# SCH_Arduino_Uno_2023-06-21.net
KiCad netlist of a schematic drawn in EasyEDA
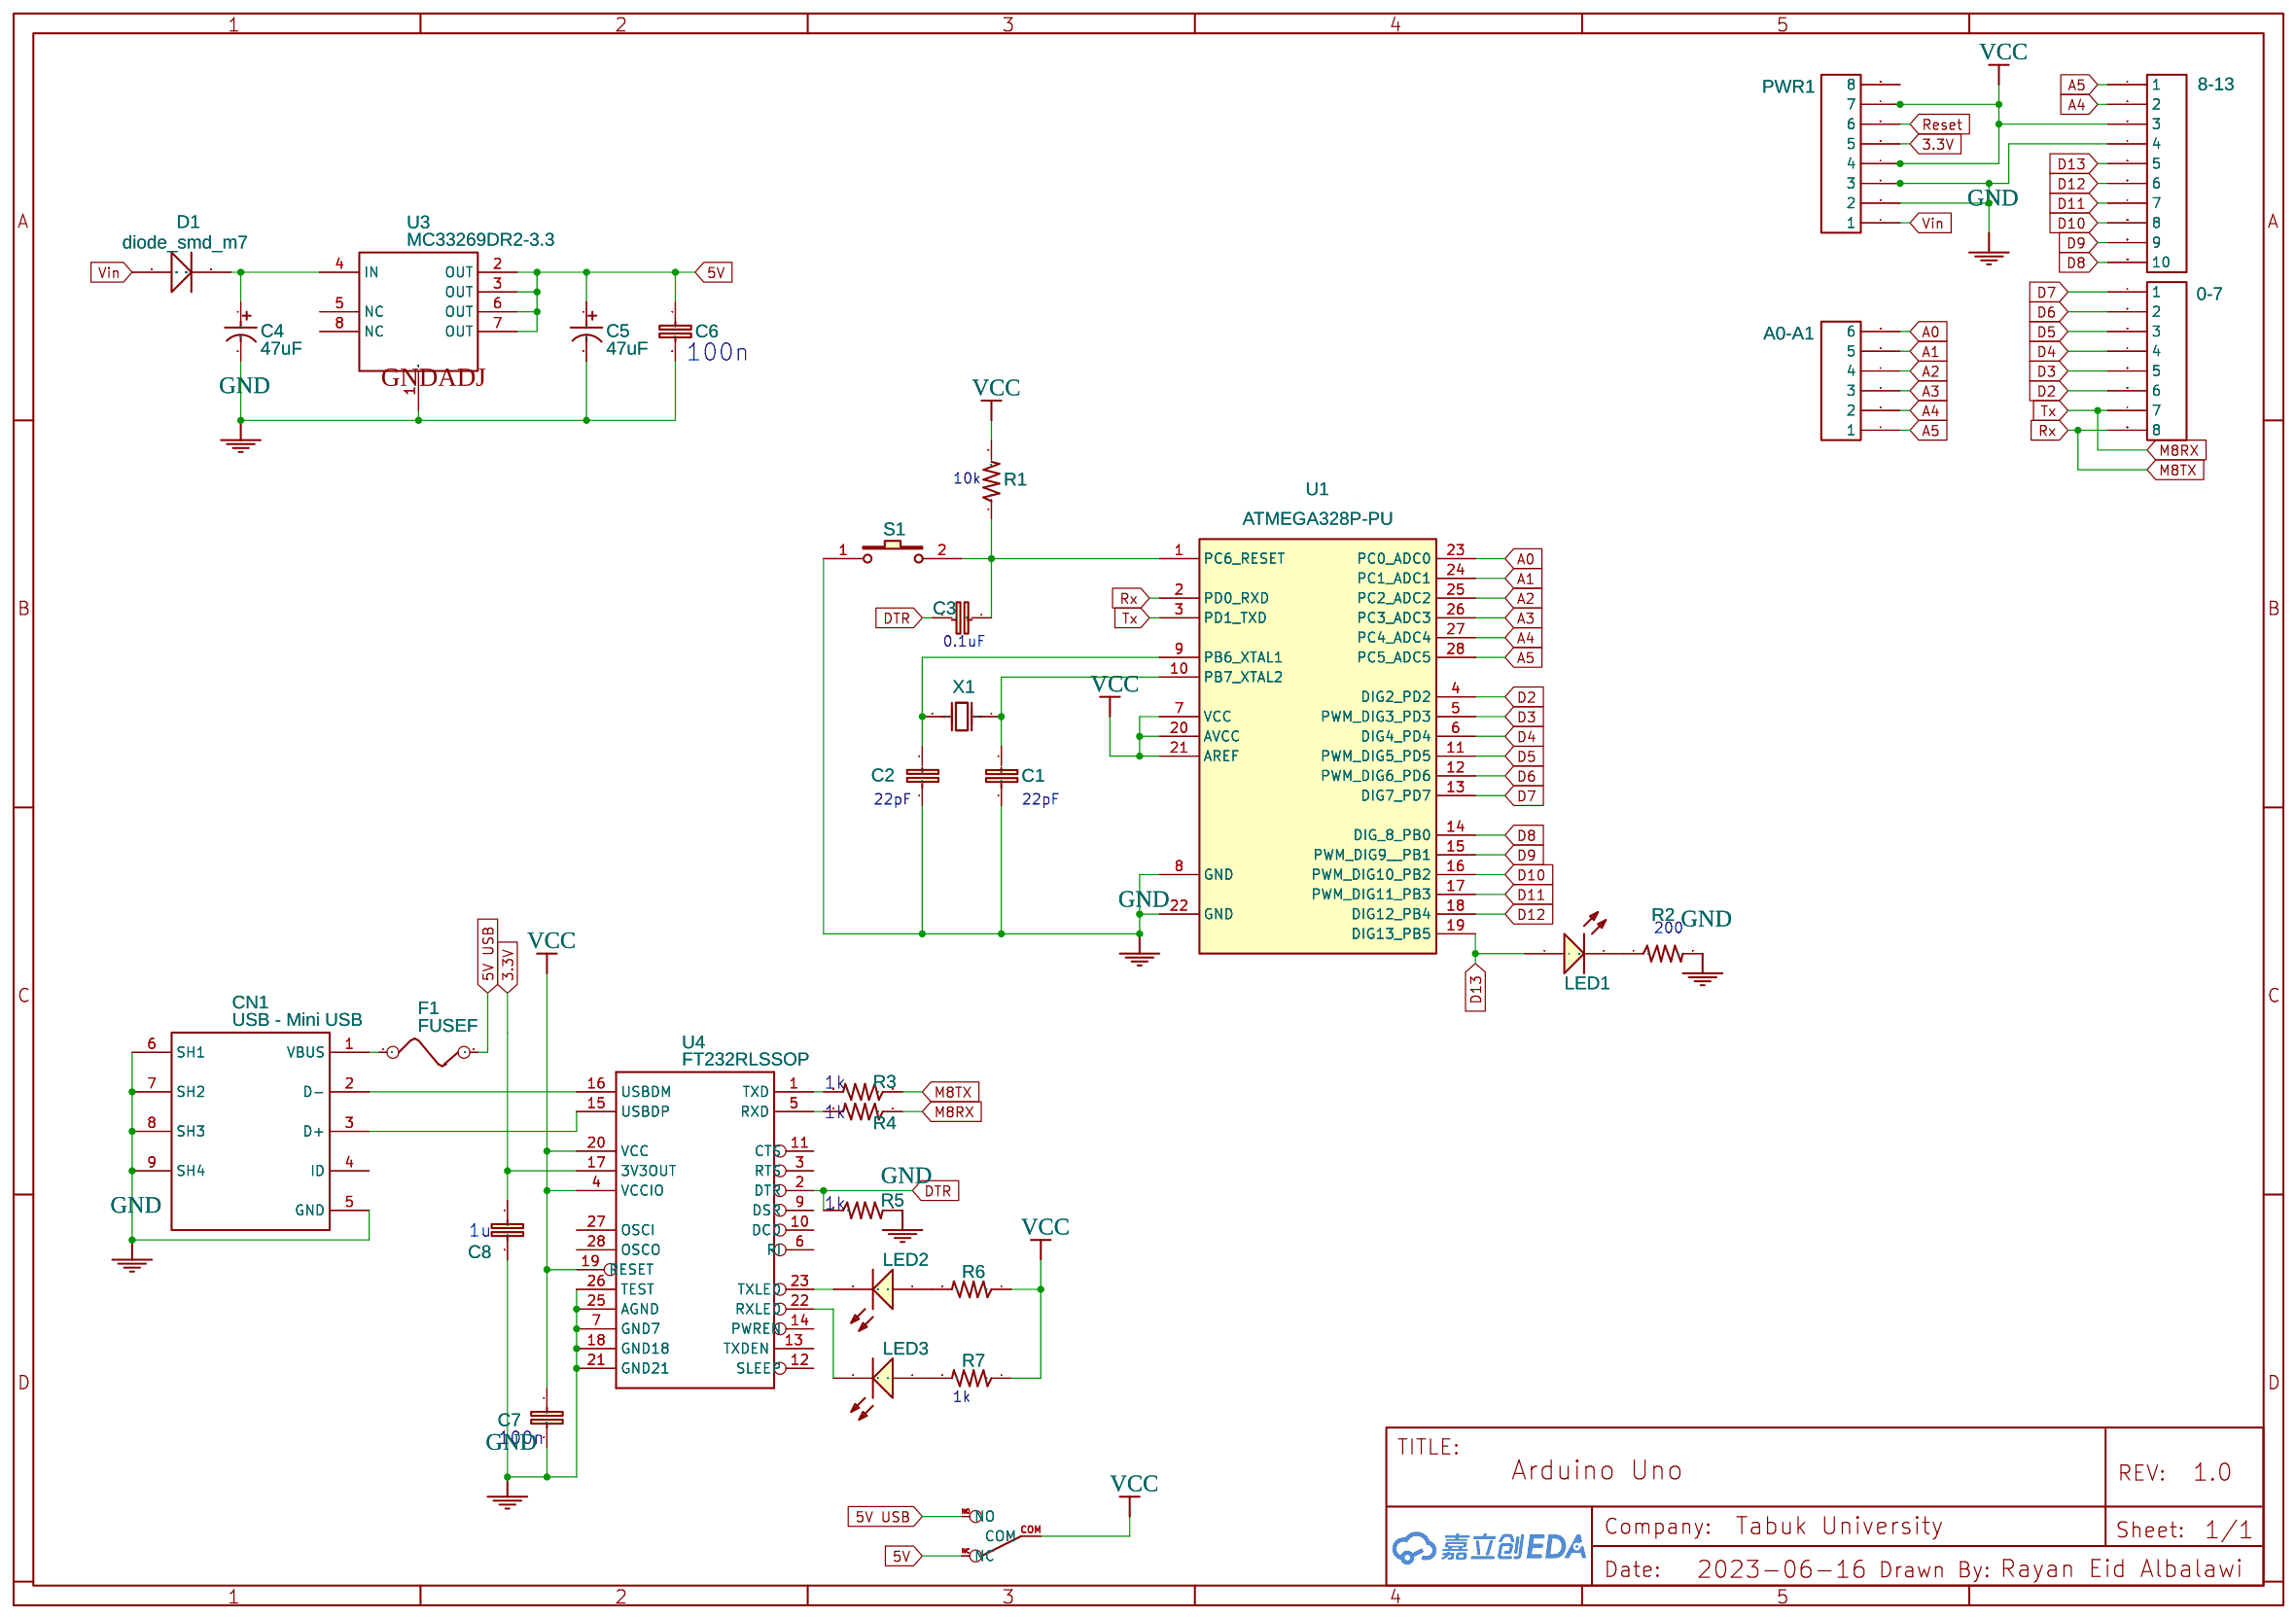
[diagram p0: schematic sheet]

(export (version "E")
  (design (tool "Eeschema 10.0.6"))
  (components
    (comp (ref "0-7")
      (value "0-7")
      (fields (field (name "BOM_Manufacturer Part") "Header2.54mm 1*8P"))
      (libsource (lib "") (part "Unknown_1070_-635"))
    )
    (comp (ref "8-13")
      (value "8-Aref")
      (fields (field (name "BOM_Manufacturer Part") "Headers  Pins2.54mm1*10P"))
      (libsource (lib "") (part "Unknown_1070_-730"))
    )
    (comp (ref "A0-A1")
      (value "Analogs")
      (fields
        (field (name "BOM_Manufacturer Part") "Header-Male-2.54_1x6")
        (field (name "BOM_Supplier Part") "C37208")
      )
      (libsource (lib "") (part "Unknown_945_-615"))
    )
    (comp (ref "C1")
      (value "CAPACITOR_NPOL-0805")
      (fields (field (name "BOM_Manufacturer Part") "?"))
      (libsource (lib "") (part "Unknown_500_-415"))
    )
    (comp (ref "C2")
      (value "CAPACITOR_NPOL-0805")
      (fields (field (name "BOM_Manufacturer Part") "?"))
      (libsource (lib "") (part "Unknown_460_-425"))
    )
    (comp (ref "C3")
      (value "CAPACITOR_NPOL-0805")
      (fields (field (name "BOM_Manufacturer Part") "?"))
      (libsource (lib "") (part "Unknown_485_-500"))
    )
    (comp (ref "C4")
      (value "47uF")
      (fields (field (name "BOM_Manufacturer Part") "EEE-HD1C470AP"))
      (libsource (lib "") (part "Unknown_115_-645"))
    )
    (comp (ref "C5")
      (value "47uF")
      (fields (field (name "BOM_Manufacturer Part") "EEE-HD1C470AP"))
      (libsource (lib "") (part "Unknown_290_-645"))
    )
    (comp (ref "C6")
      (value "CAPACITOR_NPOL-0805")
      (fields (field (name "BOM_Manufacturer Part") "?"))
      (libsource (lib "") (part "Unknown_335_-640"))
    )
    (comp (ref "C7")
      (value "CAPACITOR_NPOL-0805")
      (fields (field (name "BOM_Manufacturer Part") "?"))
      (libsource (lib "") (part "Unknown_270_-90"))
    )
    (comp (ref "C8")
      (value "CAPACITOR_NPOL-0805")
      (fields (field (name "BOM_Manufacturer Part") "?"))
      (libsource (lib "") (part "Unknown_250_-185"))
    )
    (comp (ref "CN1") (value "USB - Mini USB") (libsource (lib "") (part "Unknown_120_-250")))
    (comp (ref "D1")
      (value "diode_smd_m7")
      (fields (field (name "BOM_Manufacturer Part") "?"))
      (libsource (lib "") (part "diode_smd_m7"))
    )
    (comp (ref "F1")
      (value "FUSEF")
      (fields (field (name "BOM_Manufacturer Part") "?"))
      (libsource (lib "") (part "Unknown_215_-280"))
    )
    (comp (ref "LED1")
      (value "17-21/GHC-YR1S2/3T")
      (fields (field (name "BOM_Supplier Part") "E73546"))
      (libsource (lib "") (part "Unknown_785_-330"))
    )
    (comp (ref "LED2")
      (value "17-21/GHC-YR1S2/3T")
      (fields (field (name "BOM_Supplier Part") "E73546"))
      (libsource (lib "") (part "Unknown_445_-160"))
    )
    (comp (ref "LED3")
      (value "17-21/GHC-YR1S2/3T")
      (fields (field (name "BOM_Supplier Part") "E73546"))
      (libsource (lib "") (part "Unknown_445_-115"))
    )
    (comp (ref "PWR1")
      (value "Powers")
      (fields (field (name "BOM_Manufacturer Part") "Header2.54mm 1*8P"))
      (libsource (lib "") (part "Unknown_945_-730"))
    )
    (comp (ref "R1")
      (value "0.22OHM-1_4W-1%(0805)")
      (fields (field (name "BOM_Manufacturer Part") "?"))
      (libsource (lib "") (part "Unknown_495_-570"))
    )
    (comp (ref "R2")
      (value "200")
      (fields (field (name "BOM_Manufacturer Part") "?"))
      (libsource (lib "") (part "Unknown_835_-330"))
    )
    (comp (ref "R3")
      (value "200")
      (fields (field (name "BOM_Manufacturer Part") "?"))
      (libsource (lib "") (part "Unknown_430_-260"))
    )
    (comp (ref "R4")
      (value "200")
      (fields (field (name "BOM_Manufacturer Part") "?"))
      (libsource (lib "") (part "Unknown_430_-250"))
    )
    (comp (ref "R5")
      (value "200")
      (fields (field (name "BOM_Manufacturer Part") "?"))
      (libsource (lib "") (part "Unknown_430_-200"))
    )
    (comp (ref "R6")
      (value "200")
      (fields (field (name "BOM_Manufacturer Part") "?"))
      (libsource (lib "") (part "Unknown_485_-160"))
    )
    (comp (ref "R7")
      (value "200")
      (fields (field (name "BOM_Manufacturer Part") "?"))
      (libsource (lib "") (part "Unknown_485_-115"))
    )
    (comp (ref "S1")
      (value "Button1")
      (fields (field (name "BOM_Manufacturer Part") "?"))
      (libsource (lib "") (part "Unknown_440_-530"))
    )
    (comp (ref "SW1")
      (value "SW-SLIDE")
      (fields (field (name "BOM_Manufacturer Part") "?"))
      (libsource (lib "") (part "Unknown_490_-35"))
    )
    (comp (ref "U1")
      (value "ATMEGA328P-PU")
      (fields (field (name "BOM_Supplier Part") "C33901"))
      (libsource (lib "") (part "Unknown_640_-410"))
    )
    (comp (ref "U3")
      (value "MC33269DR2-3.3")
      (fields (field (name "BOM_Supplier Part") "C7301"))
      (libsource (lib "") (part "Unknown_205_-645"))
    )
    (comp (ref "U4")
      (value "FT232RLSSOP")
      (fields (field (name "BOM_Manufacturer Part") "?"))
      (libsource (lib "") (part "Unknown_345_-190"))
    )
    (comp (ref "X1")
      (value "16MHZ")
      (fields
        (field (name "BOM_Manufacturer Part") "X49SD16MSD2SC")
        (field (name "BOM_Supplier Part") "C16212")
      )
      (libsource (lib "") (part "Unknown_480_-450"))
    )
  )
  (nets
    (net (code "1") (name "3.3V") (class "Default")
      (node (ref "C8") (pin "1") (pinfunction "1_1") (pintype "unspecified"))
      (node (ref "PWR1") (pin "5") (pinfunction "5_5") (pintype "input"))
      (node (ref "U4") (pin "17") (pinfunction "3V3OUT_17") (pintype "output"))
    )
    (net (code "2") (name "5V") (class "Default")
      (node (ref "C5") (pin "1") (pinfunction "1_1") (pintype "input"))
      (node (ref "C6") (pin "1") (pinfunction "1_1") (pintype "unspecified"))
      (node (ref "SW1") (pin "NC") (pinfunction "NC_NC") (pintype "unspecified"))
      (node (ref "U3") (pin "2") (pinfunction "OUT_2") (pintype "passive"))
      (node (ref "U3") (pin "3") (pinfunction "OUT_3") (pintype "passive"))
      (node (ref "U3") (pin "6") (pinfunction "OUT_6") (pintype "passive"))
      (node (ref "U3") (pin "7") (pinfunction "OUT_7") (pintype "passive"))
    )
    (net (code "3") (name "5V USB") (class "Default")
      (node (ref "F1") (pin "2") (pinfunction "2_2") (pintype "unspecified"))
      (node (ref "SW1") (pin "NO") (pinfunction "NO_NO") (pintype "unspecified"))
    )
    (net (code "4") (name "A0") (class "Default")
      (node (ref "A0-A1") (pin "6") (pinfunction "6_6") (pintype "input"))
      (node (ref "U1") (pin "23") (pinfunction "PC0_ADC0_23") (pintype "bidirectional"))
    )
    (net (code "5") (name "A1") (class "Default")
      (node (ref "A0-A1") (pin "5") (pinfunction "5_5") (pintype "input"))
      (node (ref "U1") (pin "24") (pinfunction "PC1_ADC1_24") (pintype "bidirectional"))
    )
    (net (code "6") (name "A2") (class "Default")
      (node (ref "A0-A1") (pin "4") (pinfunction "4_4") (pintype "input"))
      (node (ref "U1") (pin "25") (pinfunction "PC2_ADC2_25") (pintype "bidirectional"))
    )
    (net (code "7") (name "A3") (class "Default")
      (node (ref "A0-A1") (pin "3") (pinfunction "3_3") (pintype "input"))
      (node (ref "U1") (pin "26") (pinfunction "PC3_ADC3_26") (pintype "bidirectional"))
    )
    (net (code "8") (name "A4") (class "Default")
      (node (ref "8-13") (pin "2") (pinfunction "2_2") (pintype "input"))
      (node (ref "A0-A1") (pin "2") (pinfunction "2_2") (pintype "input"))
      (node (ref "U1") (pin "27") (pinfunction "PC4_ADC4_27") (pintype "bidirectional"))
    )
    (net (code "9") (name "A5") (class "Default")
      (node (ref "8-13") (pin "1") (pinfunction "1_1") (pintype "input"))
      (node (ref "A0-A1") (pin "1") (pinfunction "1_1") (pintype "input"))
      (node (ref "U1") (pin "28") (pinfunction "PC5_ADC5_28") (pintype "bidirectional"))
    )
    (net (code "10") (name "D2") (class "Default")
      (node (ref "0-7") (pin "6") (pinfunction "6_6") (pintype "input"))
      (node (ref "U1") (pin "4") (pinfunction "DIG2_PD2_4") (pintype "bidirectional"))
    )
    (net (code "11") (name "D3") (class "Default")
      (node (ref "0-7") (pin "5") (pinfunction "5_5") (pintype "input"))
      (node (ref "U1") (pin "5") (pinfunction "PWM_DIG3_PD3_5") (pintype "bidirectional"))
    )
    (net (code "12") (name "D4") (class "Default")
      (node (ref "0-7") (pin "4") (pinfunction "4_4") (pintype "input"))
      (node (ref "U1") (pin "6") (pinfunction "DIG4_PD4_6") (pintype "bidirectional"))
    )
    (net (code "13") (name "D5") (class "Default")
      (node (ref "0-7") (pin "3") (pinfunction "3_3") (pintype "input"))
      (node (ref "U1") (pin "11") (pinfunction "PWM_DIG5_PD5_11") (pintype "bidirectional"))
    )
    (net (code "14") (name "D6") (class "Default")
      (node (ref "0-7") (pin "2") (pinfunction "2_2") (pintype "input"))
      (node (ref "U1") (pin "12") (pinfunction "PWM_DIG6_PD6_12") (pintype "bidirectional"))
    )
    (net (code "15") (name "D7") (class "Default")
      (node (ref "0-7") (pin "1") (pinfunction "1_1") (pintype "input"))
      (node (ref "U1") (pin "13") (pinfunction "DIG7_PD7_13") (pintype "bidirectional"))
    )
    (net (code "16") (name "D8") (class "Default")
      (node (ref "8-13") (pin "10") (pinfunction "10_10") (pintype "input"))
      (node (ref "U1") (pin "14") (pinfunction "DIG_8_PB0_14") (pintype "bidirectional"))
    )
    (net (code "17") (name "D9") (class "Default")
      (node (ref "8-13") (pin "9") (pinfunction "9_9") (pintype "input"))
      (node (ref "U1") (pin "15") (pinfunction "PWM_DIG9__PB1_15") (pintype "bidirectional"))
    )
    (net (code "18") (name "D10") (class "Default")
      (node (ref "8-13") (pin "8") (pinfunction "8_8") (pintype "input"))
      (node (ref "U1") (pin "16") (pinfunction "PWM_DIG10_PB2_16") (pintype "bidirectional"))
    )
    (net (code "19") (name "D11") (class "Default")
      (node (ref "8-13") (pin "7") (pinfunction "7_7") (pintype "input"))
      (node (ref "U1") (pin "17") (pinfunction "PWM_DIG11_PB3_17") (pintype "bidirectional"))
    )
    (net (code "20") (name "D12") (class "Default")
      (node (ref "8-13") (pin "6") (pinfunction "6_6") (pintype "input"))
      (node (ref "U1") (pin "18") (pinfunction "DIG12_PB4_18") (pintype "bidirectional"))
    )
    (net (code "21") (name "D13") (class "Default")
      (node (ref "8-13") (pin "5") (pinfunction "5_5") (pintype "input"))
      (node (ref "LED1") (pin "1") (pinfunction "A_1") (pintype "input"))
      (node (ref "U1") (pin "19") (pinfunction "DIG13_PB5_19") (pintype "bidirectional"))
    )
    (net (code "22") (name "DTR") (class "Default")
      (node (ref "C3") (pin "1") (pinfunction "1_1") (pintype "unspecified"))
      (node (ref "R5") (pin "1") (pinfunction "1_1") (pintype "unspecified"))
      (node (ref "U4") (pin "2") (pinfunction "DTR_2") (pintype "output"))
    )
    (net (code "23") (name "GND") (class "Default")
      (node (ref "8-13") (pin "4") (pinfunction "4_4") (pintype "input"))
      (node (ref "C1") (pin "2") (pinfunction "2_2") (pintype "unspecified"))
      (node (ref "C2") (pin "1") (pinfunction "1_1") (pintype "unspecified"))
      (node (ref "C4") (pin "2") (pinfunction "2_2") (pintype "input"))
      (node (ref "C5") (pin "2") (pinfunction "2_2") (pintype "input"))
      (node (ref "C6") (pin "2") (pinfunction "2_2") (pintype "unspecified"))
      (node (ref "C7") (pin "2") (pinfunction "2_2") (pintype "unspecified"))
      (node (ref "C8") (pin "2") (pinfunction "2_2") (pintype "unspecified"))
      (node (ref "CN1") (pin "5") (pinfunction "GND_5") (pintype "passive"))
      (node (ref "CN1") (pin "6") (pinfunction "SH1_6") (pintype "passive"))
      (node (ref "CN1") (pin "7") (pinfunction "SH2_7") (pintype "passive"))
      (node (ref "CN1") (pin "8") (pinfunction "SH3_8") (pintype "passive"))
      (node (ref "CN1") (pin "9") (pinfunction "SH4_9") (pintype "passive"))
      (node (ref "PWR1") (pin "2") (pinfunction "2_2") (pintype "input"))
      (node (ref "PWR1") (pin "3") (pinfunction "3_3") (pintype "input"))
      (node (ref "R2") (pin "2") (pinfunction "2_2") (pintype "unspecified"))
      (node (ref "R5") (pin "2") (pinfunction "2_2") (pintype "unspecified"))
      (node (ref "S1") (pin "1") (pintype "unspecified"))
      (node (ref "U1") (pin "22") (pinfunction "GND_22") (pintype "passive"))
      (node (ref "U1") (pin "8") (pinfunction "GND_8") (pintype "passive"))
      (node (ref "U3") (pin "1") (pinfunction "GNDADJ_1") (pintype "passive"))
      (node (ref "U4") (pin "18") (pinfunction "GND18_18") (pintype "passive"))
      (node (ref "U4") (pin "21") (pinfunction "GND21_21") (pintype "passive"))
      (node (ref "U4") (pin "25") (pinfunction "AGND_25") (pintype "passive"))
      (node (ref "U4") (pin "26") (pinfunction "TEST_26") (pintype "input"))
      (node (ref "U4") (pin "7") (pinfunction "GND7_7") (pintype "passive"))
    )
    (net (code "24") (name "M8RX") (class "Default")
      (node (ref "0-7") (pin "7") (pinfunction "7_7") (pintype "input"))
      (node (ref "R4") (pin "1") (pinfunction "1_1") (pintype "unspecified"))
      (node (ref "U1") (pin "3") (pinfunction "PD1_TXD_3") (pintype "bidirectional"))
    )
    (net (code "25") (name "M8TX") (class "Default")
      (node (ref "0-7") (pin "8") (pinfunction "8_8") (pintype "input"))
      (node (ref "R3") (pin "1") (pinfunction "1_1") (pintype "unspecified"))
      (node (ref "U1") (pin "2") (pinfunction "PD0_RXD_2") (pintype "bidirectional"))
    )
    (net (code "26") (name "Net-(CN1-D+)") (class "Default")
      (node (ref "CN1") (pin "3") (pinfunction "D+_3") (pintype "bidirectional"))
      (node (ref "U4") (pin "15") (pinfunction "USBDP_15") (pintype "unspecified"))
    )
    (net (code "27") (name "Net-(CN1-D-)") (class "Default")
      (node (ref "CN1") (pin "2") (pinfunction "D-_2") (pintype "bidirectional"))
      (node (ref "U4") (pin "16") (pinfunction "USBDM_16") (pintype "unspecified"))
    )
    (net (code "28") (name "Net-(CN1-VBUS)") (class "Default")
      (node (ref "CN1") (pin "1") (pinfunction "VBUS_1") (pintype "passive"))
      (node (ref "F1") (pin "1") (pinfunction "1_1") (pintype "unspecified"))
    )
    (net (code "29") (name "Net-(D1-катод)") (class "Default")
      (node (ref "C4") (pin "1") (pinfunction "1_1") (pintype "input"))
      (node (ref "D1") (pin "1") (pinfunction "катод_1") (pintype "unspecified"))
      (node (ref "U3") (pin "4") (pinfunction "IN_4") (pintype "passive"))
    )
    (net (code "30") (name "Net-(LED1-C)") (class "Default")
      (node (ref "LED1") (pin "2") (pinfunction "C_2") (pintype "input"))
      (node (ref "R2") (pin "1") (pinfunction "1_1") (pintype "unspecified"))
    )
    (net (code "31") (name "Net-(LED2-A)") (class "Default")
      (node (ref "LED2") (pin "1") (pinfunction "A_1") (pintype "input"))
      (node (ref "R6") (pin "2") (pinfunction "2_2") (pintype "unspecified"))
    )
    (net (code "32") (name "Net-(LED2-C)") (class "Default")
      (node (ref "LED2") (pin "2") (pinfunction "C_2") (pintype "input"))
      (node (ref "U4") (pin "23") (pinfunction "TXLED_23") (pintype "input"))
    )
    (net (code "33") (name "Net-(LED3-A)") (class "Default")
      (node (ref "LED3") (pin "1") (pinfunction "A_1") (pintype "input"))
      (node (ref "R7") (pin "2") (pinfunction "2_2") (pintype "unspecified"))
    )
    (net (code "34") (name "Net-(LED3-C)") (class "Default")
      (node (ref "LED3") (pin "2") (pinfunction "C_2") (pintype "input"))
      (node (ref "U4") (pin "22") (pinfunction "RXLED_22") (pintype "input"))
    )
    (net (code "35") (name "Net-(U1-PB6_XTAL1)") (class "Default")
      (node (ref "C2") (pin "2") (pinfunction "2_2") (pintype "unspecified"))
      (node (ref "U1") (pin "9") (pinfunction "PB6_XTAL1_9") (pintype "bidirectional"))
      (node (ref "X1") (pin "2") (pinfunction "OSC2_2") (pintype "input"))
    )
    (net (code "36") (name "Net-(U1-PB7_XTAL2)") (class "Default")
      (node (ref "C1") (pin "1") (pinfunction "1_1") (pintype "unspecified"))
      (node (ref "U1") (pin "10") (pinfunction "PB7_XTAL2_10") (pintype "bidirectional"))
      (node (ref "X1") (pin "1") (pinfunction "OSC1_1") (pintype "input"))
    )
    (net (code "37") (name "Net-(U1-PC6_RESET)") (class "Default")
      (node (ref "C3") (pin "2") (pinfunction "2_2") (pintype "unspecified"))
      (node (ref "R1") (pin "1") (pinfunction "1_1") (pintype "unspecified"))
      (node (ref "S1") (pin "2") (pintype "unspecified"))
      (node (ref "U1") (pin "1") (pinfunction "PC6_RESET_1") (pintype "bidirectional"))
    )
    (net (code "38") (name "Net-(U4-RXD)") (class "Default")
      (node (ref "R4") (pin "2") (pinfunction "2_2") (pintype "unspecified"))
      (node (ref "U4") (pin "5") (pinfunction "RXD_5") (pintype "input"))
    )
    (net (code "39") (name "Net-(U4-TXD)") (class "Default")
      (node (ref "R3") (pin "2") (pinfunction "2_2") (pintype "unspecified"))
      (node (ref "U4") (pin "1") (pinfunction "TXD_1") (pintype "output"))
    )
    (net (code "40") (name "Reset") (class "Default")
      (node (ref "PWR1") (pin "6") (pinfunction "6_6") (pintype "input"))
    )
    (net (code "41") (name "VCC") (class "Default")
      (node (ref "8-13") (pin "3") (pinfunction "3_3") (pintype "input"))
      (node (ref "C7") (pin "1") (pinfunction "1_1") (pintype "unspecified"))
      (node (ref "PWR1") (pin "4") (pinfunction "4_4") (pintype "input"))
      (node (ref "PWR1") (pin "7") (pinfunction "7_7") (pintype "input"))
      (node (ref "R1") (pin "2") (pinfunction "2_2") (pintype "unspecified"))
      (node (ref "R6") (pin "1") (pinfunction "1_1") (pintype "unspecified"))
      (node (ref "R7") (pin "1") (pinfunction "1_1") (pintype "unspecified"))
      (node (ref "SW1") (pin "COM") (pinfunction "COM_COM") (pintype "unspecified"))
      (node (ref "U1") (pin "20") (pinfunction "AVCC_20") (pintype "passive"))
      (node (ref "U1") (pin "21") (pinfunction "AREF_21") (pintype "passive"))
      (node (ref "U1") (pin "7") (pinfunction "VCC_7") (pintype "passive"))
      (node (ref "U4") (pin "19") (pinfunction "RESET_19") (pintype "input"))
      (node (ref "U4") (pin "20") (pinfunction "VCC_20") (pintype "passive"))
      (node (ref "U4") (pin "4") (pinfunction "VCCIO_4") (pintype "passive"))
    )
    (net (code "42") (name "Vin") (class "Default")
      (node (ref "D1") (pin "2") (pinfunction "анод_2") (pintype "unspecified"))
      (node (ref "PWR1") (pin "1") (pinfunction "1_1") (pintype "input"))
    )
    (net (code "43") (name "unconnected-(CN1-ID-Pad4)") (class "Default")
      (node (ref "CN1") (pin "4") (pinfunction "ID_4") (pintype "bidirectional"))
    )
    (net (code "44") (name "unconnected-(PWR1-Pad8)") (class "Default")
      (node (ref "PWR1") (pin "8") (pinfunction "8_8") (pintype "input"))
    )
    (net (code "45") (name "unconnected-(U3-NC-Pad5)") (class "Default")
      (node (ref "U3") (pin "5") (pinfunction "NC_5") (pintype "unspecified"))
    )
    (net (code "46") (name "unconnected-(U3-NC-Pad8)") (class "Default")
      (node (ref "U3") (pin "8") (pinfunction "NC_8") (pintype "unspecified"))
    )
    (net (code "47") (name "unconnected-(U4-CTS-Pad11)") (class "Default")
      (node (ref "U4") (pin "11") (pinfunction "CTS_11") (pintype "input"))
    )
    (net (code "48") (name "unconnected-(U4-DCD-Pad10)") (class "Default")
      (node (ref "U4") (pin "10") (pinfunction "DCD_10") (pintype "input"))
    )
    (net (code "49") (name "unconnected-(U4-DSR-Pad9)") (class "Default")
      (node (ref "U4") (pin "9") (pinfunction "DSR_9") (pintype "input"))
    )
    (net (code "50") (name "unconnected-(U4-OSCI-Pad27)") (class "Default")
      (node (ref "U4") (pin "27") (pinfunction "OSCI_27") (pintype "input"))
    )
    (net (code "51") (name "unconnected-(U4-OSCO-Pad28)") (class "Default")
      (node (ref "U4") (pin "28") (pinfunction "OSCO_28") (pintype "output"))
    )
    (net (code "52") (name "unconnected-(U4-PWREN-Pad14)") (class "Default")
      (node (ref "U4") (pin "14") (pinfunction "PWREN_14") (pintype "input"))
    )
    (net (code "53") (name "unconnected-(U4-RI-Pad6)") (class "Default")
      (node (ref "U4") (pin "6") (pinfunction "RI_6") (pintype "input"))
    )
    (net (code "54") (name "unconnected-(U4-RTS-Pad3)") (class "Default")
      (node (ref "U4") (pin "3") (pinfunction "RTS_3") (pintype "output"))
    )
    (net (code "55") (name "unconnected-(U4-SLEEP-Pad12)") (class "Default")
      (node (ref "U4") (pin "12") (pinfunction "SLEEP_12") (pintype "input"))
    )
    (net (code "56") (name "unconnected-(U4-TXDEN-Pad13)") (class "Default")
      (node (ref "U4") (pin "13") (pinfunction "TXDEN_13") (pintype "input"))
    )
  )
)
